# SCH_CARD-PCB_2024-12-08.net
KiCad netlist of a schematic drawn in EasyEDA
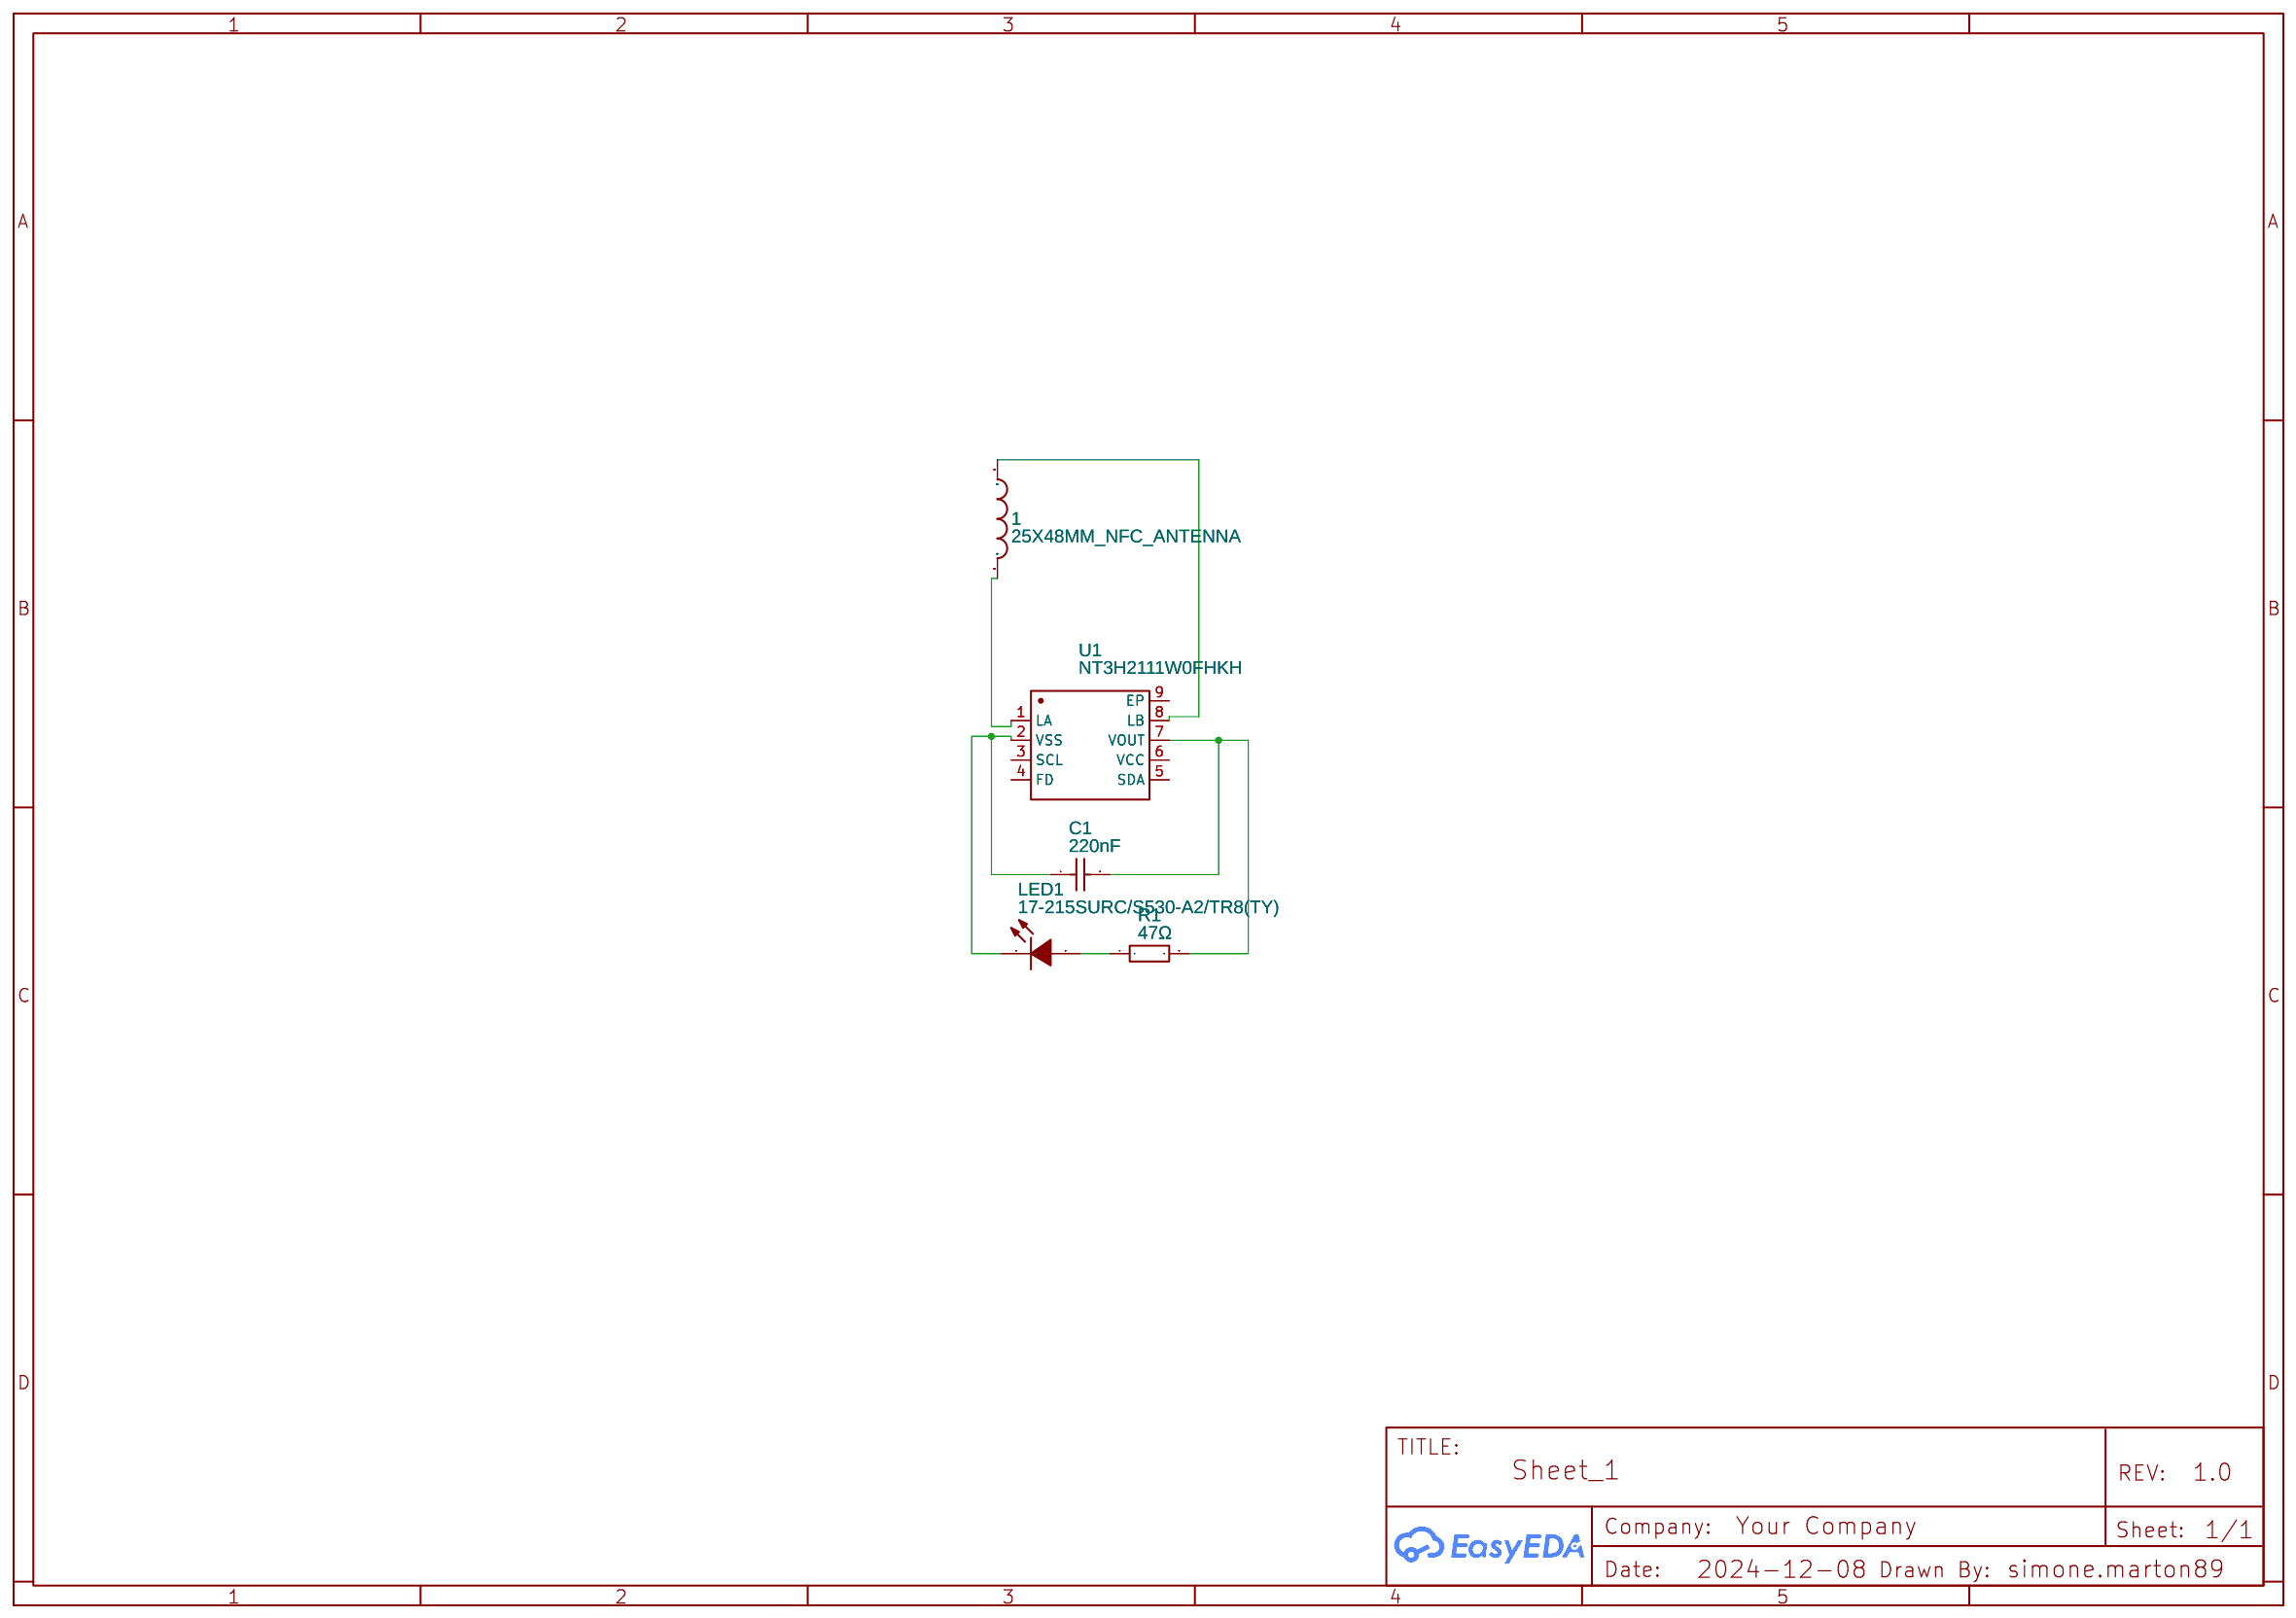
[diagram p0: schematic sheet]

(export (version "E")
  (design (tool "Eeschema 10.0.6"))
  (components
    (comp (ref "1") (value "25X48MM_NFC_ANTENNA") (libsource (lib "") (part "25X48MM_NFC_ANTENNA")))
    (comp (ref "C1")
      (value "220nF")
      (fields
        (field (name "Manufacturer Part") "CL10B224KA8NNNC")
        (field (name "Manufacturer") "SAMSUNG(三星)")
      )
      (libsource (lib "") (part "CL10B224KA8NNNC"))
    )
    (comp (ref "LED1")
      (value "17-215SURC/S530-A2/TR8(TY)")
      (fields
        (field (name "Manufacturer Part") "17-215SURC/S530-A2/TR8")
        (field (name "Manufacturer") "EVERLIGHT(亿光)")
      )
      (libsource (lib "") (part "17-215SURC/S530-A2/TR8(TY)"))
    )
    (comp (ref "R1")
      (value "47Ω")
      (fields
        (field (name "Manufacturer Part") "0603WAF470JT5E")
        (field (name "Manufacturer") "UNI-ROYAL(厚声)")
      )
      (libsource (lib "") (part "0603WAF470JT5E"))
    )
    (comp (ref "U1")
      (value "NT3H2111W0FHKH")
      (fields (field (name "Manufacturer") "NXP(恩智浦)"))
      (libsource (lib "") (part "NT3H2111W0FHKH"))
    )
  )
  (nets
    (net (code "1") (name "Net-(LED1-A)") (class "Default")
      (node (ref "LED1") (pin "2") (pinfunction "A_2") (pintype "unspecified"))
      (node (ref "R1") (pin "1") (pinfunction "1_1") (pintype "input"))
    )
    (net (code "2") (name "Net-(LED1-K)") (class "Default")
      (node (ref "C1") (pin "1") (pinfunction "1_1") (pintype "input"))
      (node (ref "LED1") (pin "1") (pinfunction "K_1") (pintype "unspecified"))
      (node (ref "U1") (pin "2") (pinfunction "VSS_2") (pintype "unspecified"))
    )
    (net (code "3") (name "Net-(U1-LA)") (class "Default")
      (node (ref "1") (pin "P$2") (pinfunction "P$2_P$2") (pintype "bidirectional"))
      (node (ref "U1") (pin "1") (pinfunction "LA_1") (pintype "unspecified"))
    )
    (net (code "4") (name "Net-(U1-LB)") (class "Default")
      (node (ref "1") (pin "P$1") (pinfunction "P$1_P$1") (pintype "bidirectional"))
      (node (ref "U1") (pin "8") (pinfunction "LB_8") (pintype "unspecified"))
    )
    (net (code "5") (name "Net-(U1-VOUT)") (class "Default")
      (node (ref "C1") (pin "2") (pinfunction "2_2") (pintype "input"))
      (node (ref "R1") (pin "2") (pinfunction "2_2") (pintype "input"))
      (node (ref "U1") (pin "7") (pinfunction "VOUT_7") (pintype "unspecified"))
    )
    (net (code "6") (name "unconnected-(U1-EP-Pad9)") (class "Default")
      (node (ref "U1") (pin "9") (pinfunction "EP_9") (pintype "unspecified"))
    )
    (net (code "7") (name "unconnected-(U1-FD-Pad4)") (class "Default")
      (node (ref "U1") (pin "4") (pinfunction "FD_4") (pintype "unspecified"))
    )
    (net (code "8") (name "unconnected-(U1-SCL-Pad3)") (class "Default")
      (node (ref "U1") (pin "3") (pinfunction "SCL_3") (pintype "unspecified"))
    )
    (net (code "9") (name "unconnected-(U1-SDA-Pad5)") (class "Default")
      (node (ref "U1") (pin "5") (pinfunction "SDA_5") (pintype "unspecified"))
    )
    (net (code "10") (name "unconnected-(U1-VCC-Pad6)") (class "Default")
      (node (ref "U1") (pin "6") (pinfunction "VCC_6") (pintype "unspecified"))
    )
  )
)
